# eagle_dibs_1.net
KiCad netlist of a schematic drawn in EAGLE
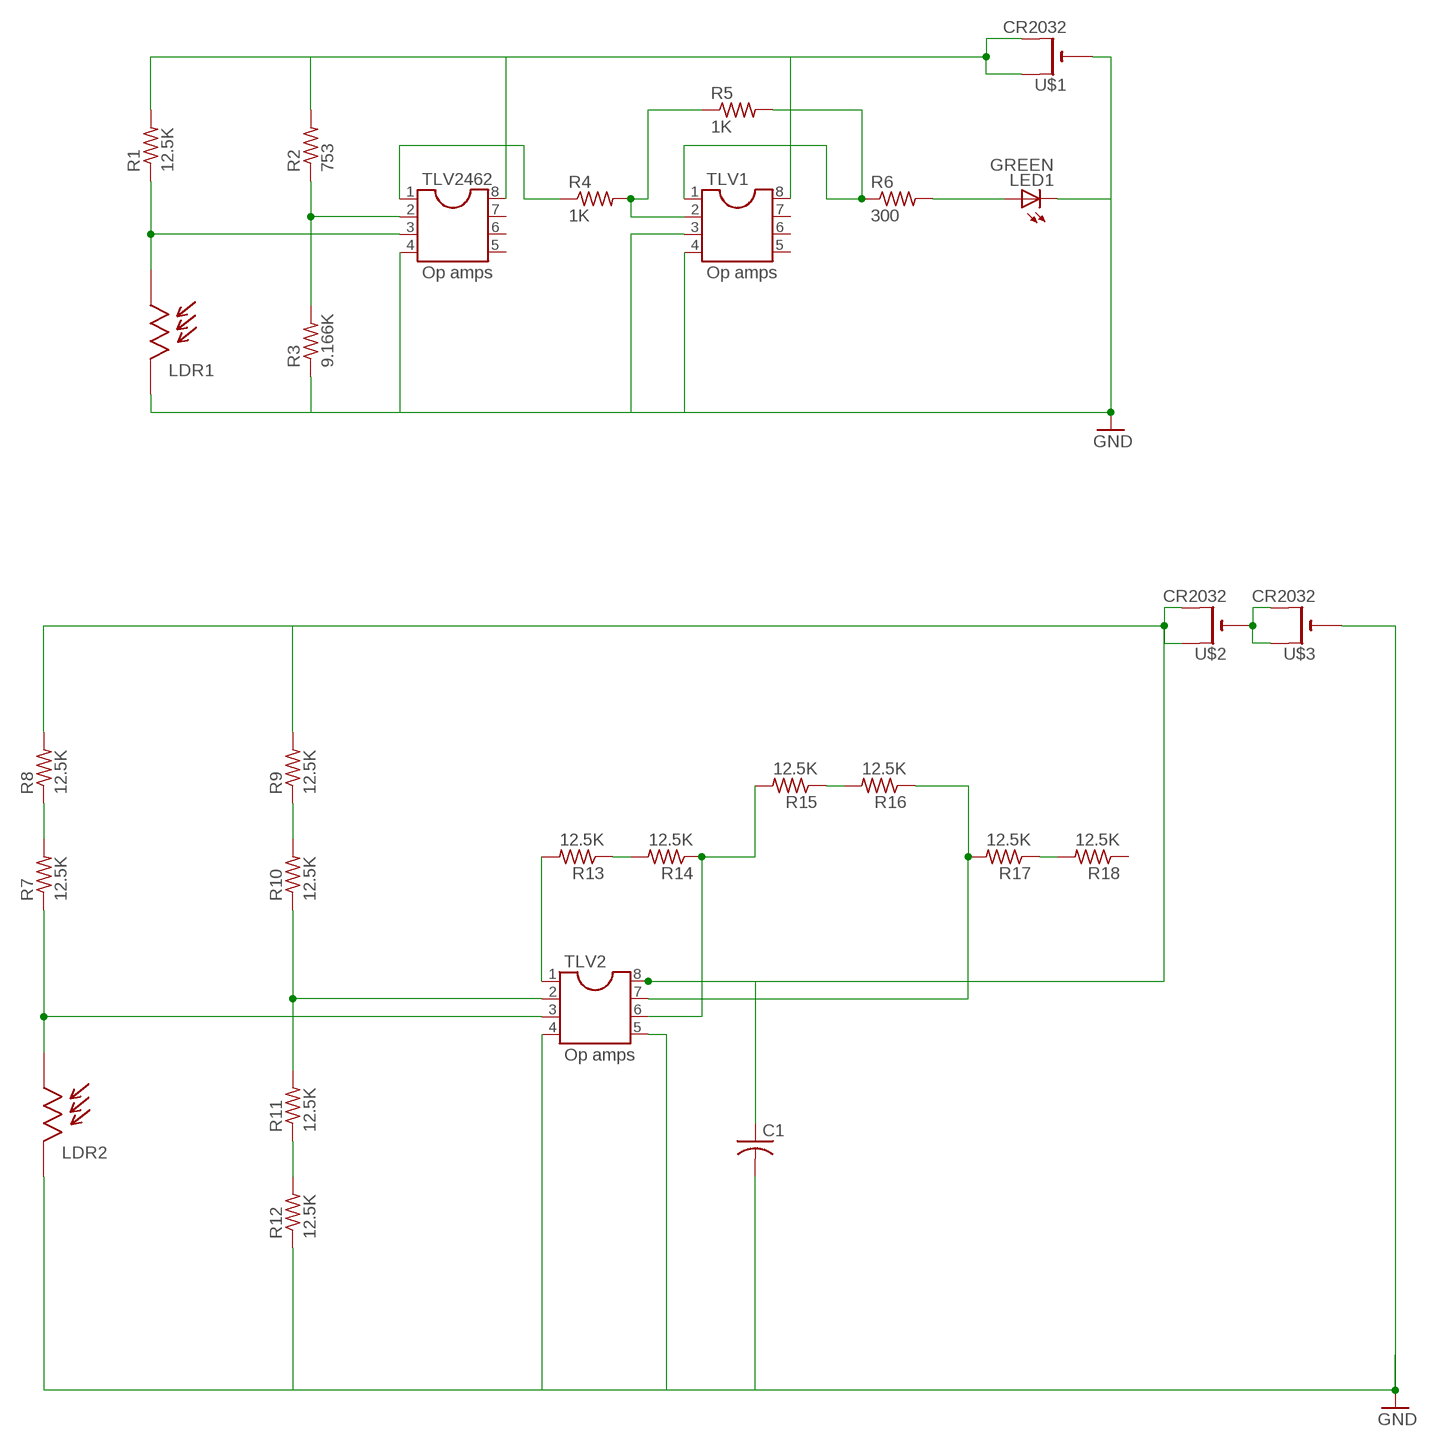
[diagram p0: schematic, sheet 1]

(export (version "E")
  (design (tool "Eeschema 10.0.6"))
  (components
    (comp (ref "C1")
      (value "C-USC0805")
      (footprint "eagle-import:C0805")
      (libsource (lib "eagle-import") (part "C-USC0805"))
    )
    (comp (ref "LDR1")
      (value "On: 555 Off: 855")
      (footprint "eagle-import:LDR3MM")
      (libsource (lib "eagle-import") (part "CDSLDR3MM"))
    )
    (comp (ref "LDR2")
      (value "On: 555 Off: 855")
      (footprint "eagle-import:LDR3MM")
      (libsource (lib "eagle-import") (part "CDSLDR3MM"))
    )
    (comp (ref "LED1")
      (value "GREEN")
      (footprint "eagle-import:LED3MM")
      (libsource (lib "eagle-import") (part "LED3MM"))
    )
    (comp (ref "R1")
      (value "12.5K")
      (footprint "eagle-import:0207_12")
      (libsource (lib "eagle-import") (part "R-US_0207/12"))
    )
    (comp (ref "R2")
      (value "753")
      (footprint "eagle-import:0207_12")
      (libsource (lib "eagle-import") (part "R-US_0207/12"))
    )
    (comp (ref "R3")
      (value "9.166K")
      (footprint "eagle-import:0207_12")
      (libsource (lib "eagle-import") (part "R-US_0207/12"))
    )
    (comp (ref "R4")
      (value "1K")
      (footprint "eagle-import:0207_12")
      (libsource (lib "eagle-import") (part "R-US_0207/12"))
    )
    (comp (ref "R5")
      (value "1K")
      (footprint "eagle-import:0207_12")
      (libsource (lib "eagle-import") (part "R-US_0207/12"))
    )
    (comp (ref "R6")
      (value "300")
      (footprint "eagle-import:0207_12")
      (libsource (lib "eagle-import") (part "R-US_0207/12"))
    )
    (comp (ref "R7")
      (value "12.5K")
      (footprint "eagle-import:0207_12")
      (libsource (lib "eagle-import") (part "R-US_0207/12"))
    )
    (comp (ref "R8")
      (value "12.5K")
      (footprint "eagle-import:0207_12")
      (libsource (lib "eagle-import") (part "R-US_0207/12"))
    )
    (comp (ref "R9")
      (value "12.5K")
      (footprint "eagle-import:0207_12")
      (libsource (lib "eagle-import") (part "R-US_0207/12"))
    )
    (comp (ref "R10")
      (value "12.5K")
      (footprint "eagle-import:0207_12")
      (libsource (lib "eagle-import") (part "R-US_0207/12"))
    )
    (comp (ref "R11")
      (value "12.5K")
      (footprint "eagle-import:0207_12")
      (libsource (lib "eagle-import") (part "R-US_0207/12"))
    )
    (comp (ref "R12")
      (value "12.5K")
      (footprint "eagle-import:0207_12")
      (libsource (lib "eagle-import") (part "R-US_0207/12"))
    )
    (comp (ref "R13")
      (value "12.5K")
      (footprint "eagle-import:0207_12")
      (libsource (lib "eagle-import") (part "R-US_0207/12"))
    )
    (comp (ref "R14")
      (value "12.5K")
      (footprint "eagle-import:0207_12")
      (libsource (lib "eagle-import") (part "R-US_0207/12"))
    )
    (comp (ref "R15")
      (value "12.5K")
      (footprint "eagle-import:0207_12")
      (libsource (lib "eagle-import") (part "R-US_0207/12"))
    )
    (comp (ref "R16")
      (value "12.5K")
      (footprint "eagle-import:0207_12")
      (libsource (lib "eagle-import") (part "R-US_0207/12"))
    )
    (comp (ref "R17")
      (value "12.5K")
      (footprint "eagle-import:0207_12")
      (libsource (lib "eagle-import") (part "R-US_0207/12"))
    )
    (comp (ref "R18")
      (value "12.5K")
      (footprint "eagle-import:0207_12")
      (libsource (lib "eagle-import") (part "R-US_0207/12"))
    )
    (comp (ref "TLV1")
      (value "Op amps")
      (footprint "eagle-import:SOCKET-08")
      (libsource (lib "eagle-import") (part "DIL8S"))
    )
    (comp (ref "TLV2")
      (value "Op amps")
      (footprint "eagle-import:SOCKET-08")
      (libsource (lib "eagle-import") (part "DIL8S"))
    )
    (comp (ref "TLV2462")
      (value "Op amps")
      (footprint "eagle-import:SOCKET-08")
      (libsource (lib "eagle-import") (part "DIL8S"))
    )
    (comp (ref "U$1")
      (value "CR2032")
      (footprint "eagle-import:CR2032-THRU")
      (libsource (lib "eagle-import") (part "CR2032THM"))
    )
    (comp (ref "U$2")
      (value "CR2032")
      (footprint "eagle-import:CR2032-THRU")
      (libsource (lib "eagle-import") (part "CR2032THM"))
    )
    (comp (ref "U$3")
      (value "CR2032")
      (footprint "eagle-import:CR2032-THRU")
      (libsource (lib "eagle-import") (part "CR2032THM"))
    )
  )
  (nets
    (net (code "1") (name "GND") (class "Default")
      (node (ref "C1") (pin "2") (pinfunction "2_2") (pintype "passive"))
      (node (ref "LDR1") (pin "P$2") (pinfunction "P$2_P$2") (pintype "bidirectional"))
      (node (ref "LDR2") (pin "P$2") (pinfunction "P$2_P$2") (pintype "bidirectional"))
      (node (ref "LED1") (pin "K") (pinfunction "C_K") (pintype "passive"))
      (node (ref "R12") (pin "1") (pinfunction "1_1") (pintype "passive"))
      (node (ref "R3") (pin "1") (pinfunction "1_1") (pintype "passive"))
      (node (ref "TLV1") (pin "3") (pinfunction "3_3") (pintype "passive"))
      (node (ref "TLV1") (pin "4") (pinfunction "4_4") (pintype "passive"))
      (node (ref "TLV2") (pin "4") (pinfunction "4_4") (pintype "passive"))
      (node (ref "TLV2") (pin "5") (pinfunction "5_5") (pintype "passive"))
      (node (ref "TLV2462") (pin "4") (pinfunction "4_4") (pintype "passive"))
      (node (ref "U$1") (pin "-") (pinfunction "-_-") (pintype "passive"))
      (node (ref "U$3") (pin "-") (pinfunction "-_-") (pintype "passive"))
    )
    (net (code "2") (name "Net-(LDR1-PadP$1)") (class "Default")
      (node (ref "LDR1") (pin "P$1") (pinfunction "P$1_P$1") (pintype "bidirectional"))
      (node (ref "R1") (pin "1") (pinfunction "1_1") (pintype "passive"))
      (node (ref "TLV2462") (pin "3") (pinfunction "3_3") (pintype "passive"))
    )
    (net (code "3") (name "Net-(LDR2-PadP$1)") (class "Default")
      (node (ref "LDR2") (pin "P$1") (pinfunction "P$1_P$1") (pintype "bidirectional"))
      (node (ref "R7") (pin "1") (pinfunction "1_1") (pintype "passive"))
      (node (ref "TLV2") (pin "3") (pinfunction "3_3") (pintype "passive"))
    )
    (net (code "4") (name "Net-(LED1-PadA)") (class "Default")
      (node (ref "LED1") (pin "A") (pinfunction "A_A") (pintype "passive"))
      (node (ref "R6") (pin "2") (pinfunction "2_2") (pintype "passive"))
    )
    (net (code "5") (name "Net-(R2-Pad1)") (class "Default")
      (node (ref "R2") (pin "1") (pinfunction "1_1") (pintype "passive"))
      (node (ref "R3") (pin "2") (pinfunction "2_2") (pintype "passive"))
      (node (ref "TLV2462") (pin "2") (pinfunction "2_2") (pintype "passive"))
    )
    (net (code "6") (name "Net-(R4-Pad1)") (class "Default")
      (node (ref "R4") (pin "1") (pinfunction "1_1") (pintype "passive"))
      (node (ref "TLV2462") (pin "1") (pinfunction "1_1") (pintype "passive"))
    )
    (net (code "7") (name "Net-(R4-Pad2)") (class "Default")
      (node (ref "R4") (pin "2") (pinfunction "2_2") (pintype "passive"))
      (node (ref "R5") (pin "1") (pinfunction "1_1") (pintype "passive"))
      (node (ref "TLV1") (pin "2") (pinfunction "2_2") (pintype "passive"))
    )
    (net (code "8") (name "Net-(R5-Pad2)") (class "Default")
      (node (ref "R5") (pin "2") (pinfunction "2_2") (pintype "passive"))
      (node (ref "R6") (pin "1") (pinfunction "1_1") (pintype "passive"))
      (node (ref "TLV1") (pin "1") (pinfunction "1_1") (pintype "passive"))
    )
    (net (code "9") (name "Net-(R7-Pad2)") (class "Default")
      (node (ref "R7") (pin "2") (pinfunction "2_2") (pintype "passive"))
      (node (ref "R8") (pin "1") (pinfunction "1_1") (pintype "passive"))
    )
    (net (code "10") (name "Net-(R10-Pad1)") (class "Default")
      (node (ref "R10") (pin "1") (pinfunction "1_1") (pintype "passive"))
      (node (ref "R11") (pin "2") (pinfunction "2_2") (pintype "passive"))
      (node (ref "TLV2") (pin "2") (pinfunction "2_2") (pintype "passive"))
    )
    (net (code "11") (name "Net-(R10-Pad2)") (class "Default")
      (node (ref "R10") (pin "2") (pinfunction "2_2") (pintype "passive"))
      (node (ref "R9") (pin "1") (pinfunction "1_1") (pintype "passive"))
    )
    (net (code "12") (name "Net-(R11-Pad1)") (class "Default")
      (node (ref "R11") (pin "1") (pinfunction "1_1") (pintype "passive"))
      (node (ref "R12") (pin "2") (pinfunction "2_2") (pintype "passive"))
    )
    (net (code "13") (name "Net-(R13-Pad1)") (class "Default")
      (node (ref "R13") (pin "1") (pinfunction "1_1") (pintype "passive"))
      (node (ref "R14") (pin "2") (pinfunction "2_2") (pintype "passive"))
    )
    (net (code "14") (name "Net-(R13-Pad2)") (class "Default")
      (node (ref "R13") (pin "2") (pinfunction "2_2") (pintype "passive"))
      (node (ref "TLV2") (pin "1") (pinfunction "1_1") (pintype "passive"))
    )
    (net (code "15") (name "Net-(R14-Pad1)") (class "Default")
      (node (ref "R14") (pin "1") (pinfunction "1_1") (pintype "passive"))
      (node (ref "R15") (pin "2") (pinfunction "2_2") (pintype "passive"))
      (node (ref "TLV2") (pin "6") (pinfunction "6_6") (pintype "passive"))
    )
    (net (code "16") (name "Net-(R15-Pad1)") (class "Default")
      (node (ref "R15") (pin "1") (pinfunction "1_1") (pintype "passive"))
      (node (ref "R16") (pin "2") (pinfunction "2_2") (pintype "passive"))
    )
    (net (code "17") (name "Net-(R16-Pad1)") (class "Default")
      (node (ref "R16") (pin "1") (pinfunction "1_1") (pintype "passive"))
      (node (ref "R17") (pin "2") (pinfunction "2_2") (pintype "passive"))
      (node (ref "TLV2") (pin "7") (pinfunction "7_7") (pintype "passive"))
    )
    (net (code "18") (name "Net-(R17-Pad1)") (class "Default")
      (node (ref "R17") (pin "1") (pinfunction "1_1") (pintype "passive"))
      (node (ref "R18") (pin "2") (pinfunction "2_2") (pintype "passive"))
    )
    (net (code "19") (name "Net-(U$1-+)") (class "Default")
      (node (ref "R1") (pin "2") (pinfunction "2_2") (pintype "passive"))
      (node (ref "R2") (pin "2") (pinfunction "2_2") (pintype "passive"))
      (node (ref "TLV1") (pin "8") (pinfunction "8_8") (pintype "passive"))
      (node (ref "TLV2462") (pin "8") (pinfunction "8_8") (pintype "passive"))
      (node (ref "U$1") (pin "+1") (pinfunction "+_+1") (pintype "passive"))
      (node (ref "U$1") (pin "+2") (pinfunction "+1_+2") (pintype "passive"))
    )
    (net (code "20") (name "Net-(U$2-+)") (class "Default")
      (node (ref "C1") (pin "1") (pinfunction "1_1") (pintype "passive"))
      (node (ref "R8") (pin "2") (pinfunction "2_2") (pintype "passive"))
      (node (ref "R9") (pin "2") (pinfunction "2_2") (pintype "passive"))
      (node (ref "TLV2") (pin "8") (pinfunction "8_8") (pintype "passive"))
      (node (ref "U$2") (pin "+1") (pinfunction "+_+1") (pintype "passive"))
      (node (ref "U$2") (pin "+2") (pinfunction "+1_+2") (pintype "passive"))
    )
    (net (code "21") (name "Net-(U$3-+)") (class "Default")
      (node (ref "U$2") (pin "-") (pinfunction "-_-") (pintype "passive"))
      (node (ref "U$3") (pin "+1") (pinfunction "+_+1") (pintype "passive"))
      (node (ref "U$3") (pin "+2") (pinfunction "+1_+2") (pintype "passive"))
    )
    (net (code "22") (name "unconnected-(R18-Pad1)") (class "Default")
      (node (ref "R18") (pin "1") (pinfunction "1_1") (pintype "passive"))
    )
    (net (code "23") (name "unconnected-(TLV1-Pad5)") (class "Default")
      (node (ref "TLV1") (pin "5") (pinfunction "5_5") (pintype "passive"))
    )
    (net (code "24") (name "unconnected-(TLV1-Pad6)") (class "Default")
      (node (ref "TLV1") (pin "6") (pinfunction "6_6") (pintype "passive"))
    )
    (net (code "25") (name "unconnected-(TLV1-Pad7)") (class "Default")
      (node (ref "TLV1") (pin "7") (pinfunction "7_7") (pintype "passive"))
    )
    (net (code "26") (name "unconnected-(TLV2462-Pad5)") (class "Default")
      (node (ref "TLV2462") (pin "5") (pinfunction "5_5") (pintype "passive"))
    )
    (net (code "27") (name "unconnected-(TLV2462-Pad6)") (class "Default")
      (node (ref "TLV2462") (pin "6") (pinfunction "6_6") (pintype "passive"))
    )
    (net (code "28") (name "unconnected-(TLV2462-Pad7)") (class "Default")
      (node (ref "TLV2462") (pin "7") (pinfunction "7_7") (pintype "passive"))
    )
  )
)
